# SMD_cree_driver_led-mosfet0023.net
KiCad netlist of a schematic drawn in EAGLE
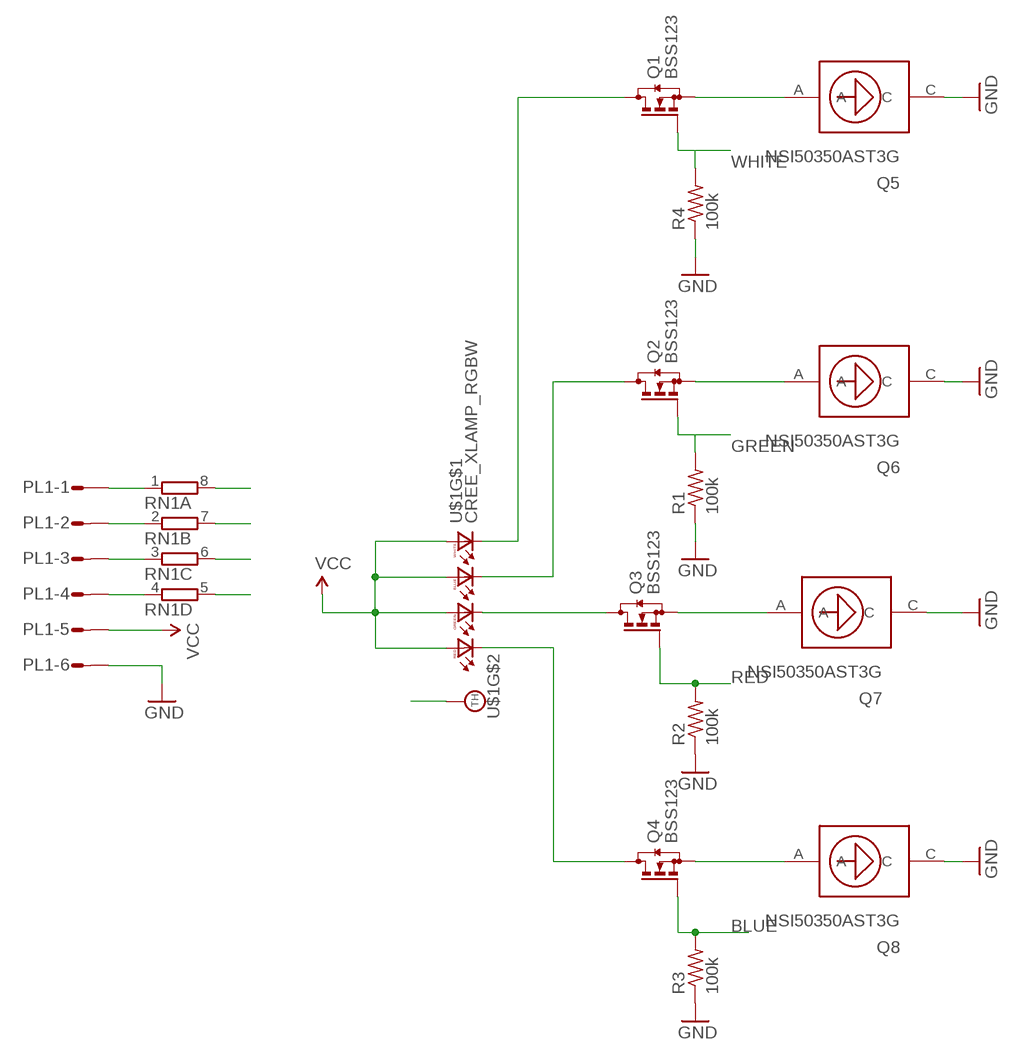
[diagram p0: schematic, sheet 1]

(export (version "E")
  (design (tool "Eeschema 10.0.6"))
  (components
    (comp (ref "PL1")
      (value "DF3-06R")
      (footprint "eagle-import:DF3R-06")
      (libsource (lib "eagle-import") (part "DF3-06R"))
    )
    (comp (ref "Q1")
      (value "BSS123")
      (footprint "eagle-import:SOT23")
      (libsource (lib "eagle-import") (part "BSS123"))
    )
    (comp (ref "Q2")
      (value "BSS123")
      (footprint "eagle-import:SOT23")
      (libsource (lib "eagle-import") (part "BSS123"))
    )
    (comp (ref "Q3")
      (value "BSS123")
      (footprint "eagle-import:SOT23")
      (libsource (lib "eagle-import") (part "BSS123"))
    )
    (comp (ref "Q4")
      (value "BSS123")
      (footprint "eagle-import:SOT23")
      (libsource (lib "eagle-import") (part "BSS123"))
    )
    (comp (ref "Q5")
      (value "NSI50350AST3G")
      (footprint "eagle-import:SMC-2")
      (libsource (lib "eagle-import") (part "NSI50350AST3G"))
    )
    (comp (ref "Q6")
      (value "NSI50350AST3G")
      (footprint "eagle-import:SMC-2")
      (libsource (lib "eagle-import") (part "NSI50350AST3G"))
    )
    (comp (ref "Q7")
      (value "NSI50350AST3G")
      (footprint "eagle-import:SMC-2")
      (libsource (lib "eagle-import") (part "NSI50350AST3G"))
    )
    (comp (ref "Q8")
      (value "NSI50350AST3G")
      (footprint "eagle-import:SMC-2")
      (libsource (lib "eagle-import") (part "NSI50350AST3G"))
    )
    (comp (ref "R1")
      (value "100k")
      (footprint "eagle-import:R0402")
      (libsource (lib "eagle-import") (part "R-US_R0402"))
    )
    (comp (ref "R2")
      (value "100k")
      (footprint "eagle-import:R0402")
      (libsource (lib "eagle-import") (part "R-US_R0402"))
    )
    (comp (ref "R3")
      (value "100k")
      (footprint "eagle-import:R0402")
      (libsource (lib "eagle-import") (part "R-US_R0402"))
    )
    (comp (ref "R4")
      (value "100k")
      (footprint "eagle-import:R0402")
      (libsource (lib "eagle-import") (part "R-US_R0402"))
    )
    (comp (ref "RN1")
      (value "4R-N0603-ARC")
      (footprint "eagle-import:0603-ARC")
      (libsource (lib "eagle-import") (part "4R-N0603-ARC"))
    )
    (comp (ref "U$1")
      (value "CREE_XLAMP_RGBW")
      (footprint "eagle-import:CREE_XLAMP_XML")
      (libsource (lib "eagle-import") (part "CREE_XLAMP_RGBW"))
    )
  )
  (nets
    (net (code "1") (name "/BLUE") (class "Default")
      (node (ref "Q4") (pin "1") (pinfunction "G_1") (pintype "passive"))
      (node (ref "R3") (pin "2") (pinfunction "2_2") (pintype "passive"))
      (node (ref "RN1") (pin "7") (pinfunction "2_7") (pintype "passive"))
    )
    (net (code "2") (name "/GREEN") (class "Default")
      (node (ref "Q2") (pin "1") (pinfunction "G_1") (pintype "passive"))
      (node (ref "R1") (pin "2") (pinfunction "2_2") (pintype "passive"))
      (node (ref "RN1") (pin "6") (pinfunction "2_6") (pintype "passive"))
    )
    (net (code "3") (name "/RED") (class "Default")
      (node (ref "Q3") (pin "1") (pinfunction "G_1") (pintype "passive"))
      (node (ref "R2") (pin "2") (pinfunction "2_2") (pintype "passive"))
      (node (ref "RN1") (pin "5") (pinfunction "2_5") (pintype "passive"))
    )
    (net (code "4") (name "/WHITE") (class "Default")
      (node (ref "Q1") (pin "1") (pinfunction "G_1") (pintype "passive"))
      (node (ref "R4") (pin "2") (pinfunction "2_2") (pintype "passive"))
      (node (ref "RN1") (pin "8") (pinfunction "2_8") (pintype "passive"))
    )
    (net (code "5") (name "GND") (class "Default")
      (node (ref "PL1") (pin "6") (pinfunction "S_6") (pintype "passive"))
      (node (ref "Q5") (pin "C") (pinfunction "C_C") (pintype "bidirectional"))
      (node (ref "Q6") (pin "C") (pinfunction "C_C") (pintype "bidirectional"))
      (node (ref "Q7") (pin "C") (pinfunction "C_C") (pintype "bidirectional"))
      (node (ref "Q8") (pin "C") (pinfunction "C_C") (pintype "bidirectional"))
      (node (ref "R1") (pin "1") (pinfunction "1_1") (pintype "passive"))
      (node (ref "R2") (pin "1") (pinfunction "1_1") (pintype "passive"))
      (node (ref "R3") (pin "1") (pinfunction "1_1") (pintype "passive"))
      (node (ref "R4") (pin "1") (pinfunction "1_1") (pintype "passive"))
    )
    (net (code "6") (name "Net-(PL1A-S)") (class "Default")
      (node (ref "PL1") (pin "1") (pinfunction "S_1") (pintype "passive"))
      (node (ref "RN1") (pin "1") (pinfunction "1_1") (pintype "passive"))
    )
    (net (code "7") (name "Net-(PL1B-S)") (class "Default")
      (node (ref "PL1") (pin "2") (pinfunction "S_2") (pintype "passive"))
      (node (ref "RN1") (pin "2") (pinfunction "1_2") (pintype "passive"))
    )
    (net (code "8") (name "Net-(PL1C-S)") (class "Default")
      (node (ref "PL1") (pin "3") (pinfunction "S_3") (pintype "passive"))
      (node (ref "RN1") (pin "3") (pinfunction "1_3") (pintype "passive"))
    )
    (net (code "9") (name "Net-(PL1D-S)") (class "Default")
      (node (ref "PL1") (pin "4") (pinfunction "S_4") (pintype "passive"))
      (node (ref "RN1") (pin "4") (pinfunction "1_4") (pintype "passive"))
    )
    (net (code "10") (name "Net-(Q1-D)") (class "Default")
      (node (ref "Q1") (pin "3") (pinfunction "D_3") (pintype "passive"))
      (node (ref "U$1") (pin "5") (pinfunction "WC_5") (pintype "passive"))
    )
    (net (code "11") (name "Net-(Q1-S)") (class "Default")
      (node (ref "Q1") (pin "2") (pinfunction "S_2") (pintype "passive"))
      (node (ref "Q5") (pin "A") (pinfunction "A_A") (pintype "bidirectional"))
    )
    (net (code "12") (name "Net-(Q2-D)") (class "Default")
      (node (ref "Q2") (pin "3") (pinfunction "D_3") (pintype "passive"))
      (node (ref "U$1") (pin "6") (pinfunction "BC_6") (pintype "passive"))
    )
    (net (code "13") (name "Net-(Q2-S)") (class "Default")
      (node (ref "Q2") (pin "2") (pinfunction "S_2") (pintype "passive"))
      (node (ref "Q6") (pin "A") (pinfunction "A_A") (pintype "bidirectional"))
    )
    (net (code "14") (name "Net-(Q3-D)") (class "Default")
      (node (ref "Q3") (pin "3") (pinfunction "D_3") (pintype "passive"))
      (node (ref "U$1") (pin "7") (pinfunction "GC_7") (pintype "passive"))
    )
    (net (code "15") (name "Net-(Q3-S)") (class "Default")
      (node (ref "Q3") (pin "2") (pinfunction "S_2") (pintype "passive"))
      (node (ref "Q7") (pin "A") (pinfunction "A_A") (pintype "bidirectional"))
    )
    (net (code "16") (name "Net-(Q4-D)") (class "Default")
      (node (ref "Q4") (pin "3") (pinfunction "D_3") (pintype "passive"))
      (node (ref "U$1") (pin "8") (pinfunction "RC_8") (pintype "passive"))
    )
    (net (code "17") (name "Net-(Q4-S)") (class "Default")
      (node (ref "Q4") (pin "2") (pinfunction "S_2") (pintype "passive"))
      (node (ref "Q8") (pin "A") (pinfunction "A_A") (pintype "bidirectional"))
    )
    (net (code "18") (name "VCC") (class "Default")
      (node (ref "PL1") (pin "5") (pinfunction "S_5") (pintype "passive"))
      (node (ref "U$1") (pin "1") (pinfunction "RA_1") (pintype "passive"))
      (node (ref "U$1") (pin "2") (pinfunction "GA_2") (pintype "passive"))
      (node (ref "U$1") (pin "3") (pinfunction "BA_3") (pintype "passive"))
      (node (ref "U$1") (pin "4") (pinfunction "WA_4") (pintype "passive"))
    )
    (net (code "19") (name "unconnected-(U$1B-TH-PadP$1)") (class "Default")
      (node (ref "U$1") (pin "P$1") (pinfunction "TH_P$1") (pintype "passive"))
    )
  )
)
